# LuMini_3Inch.net
KiCad netlist of a schematic drawn in EAGLE
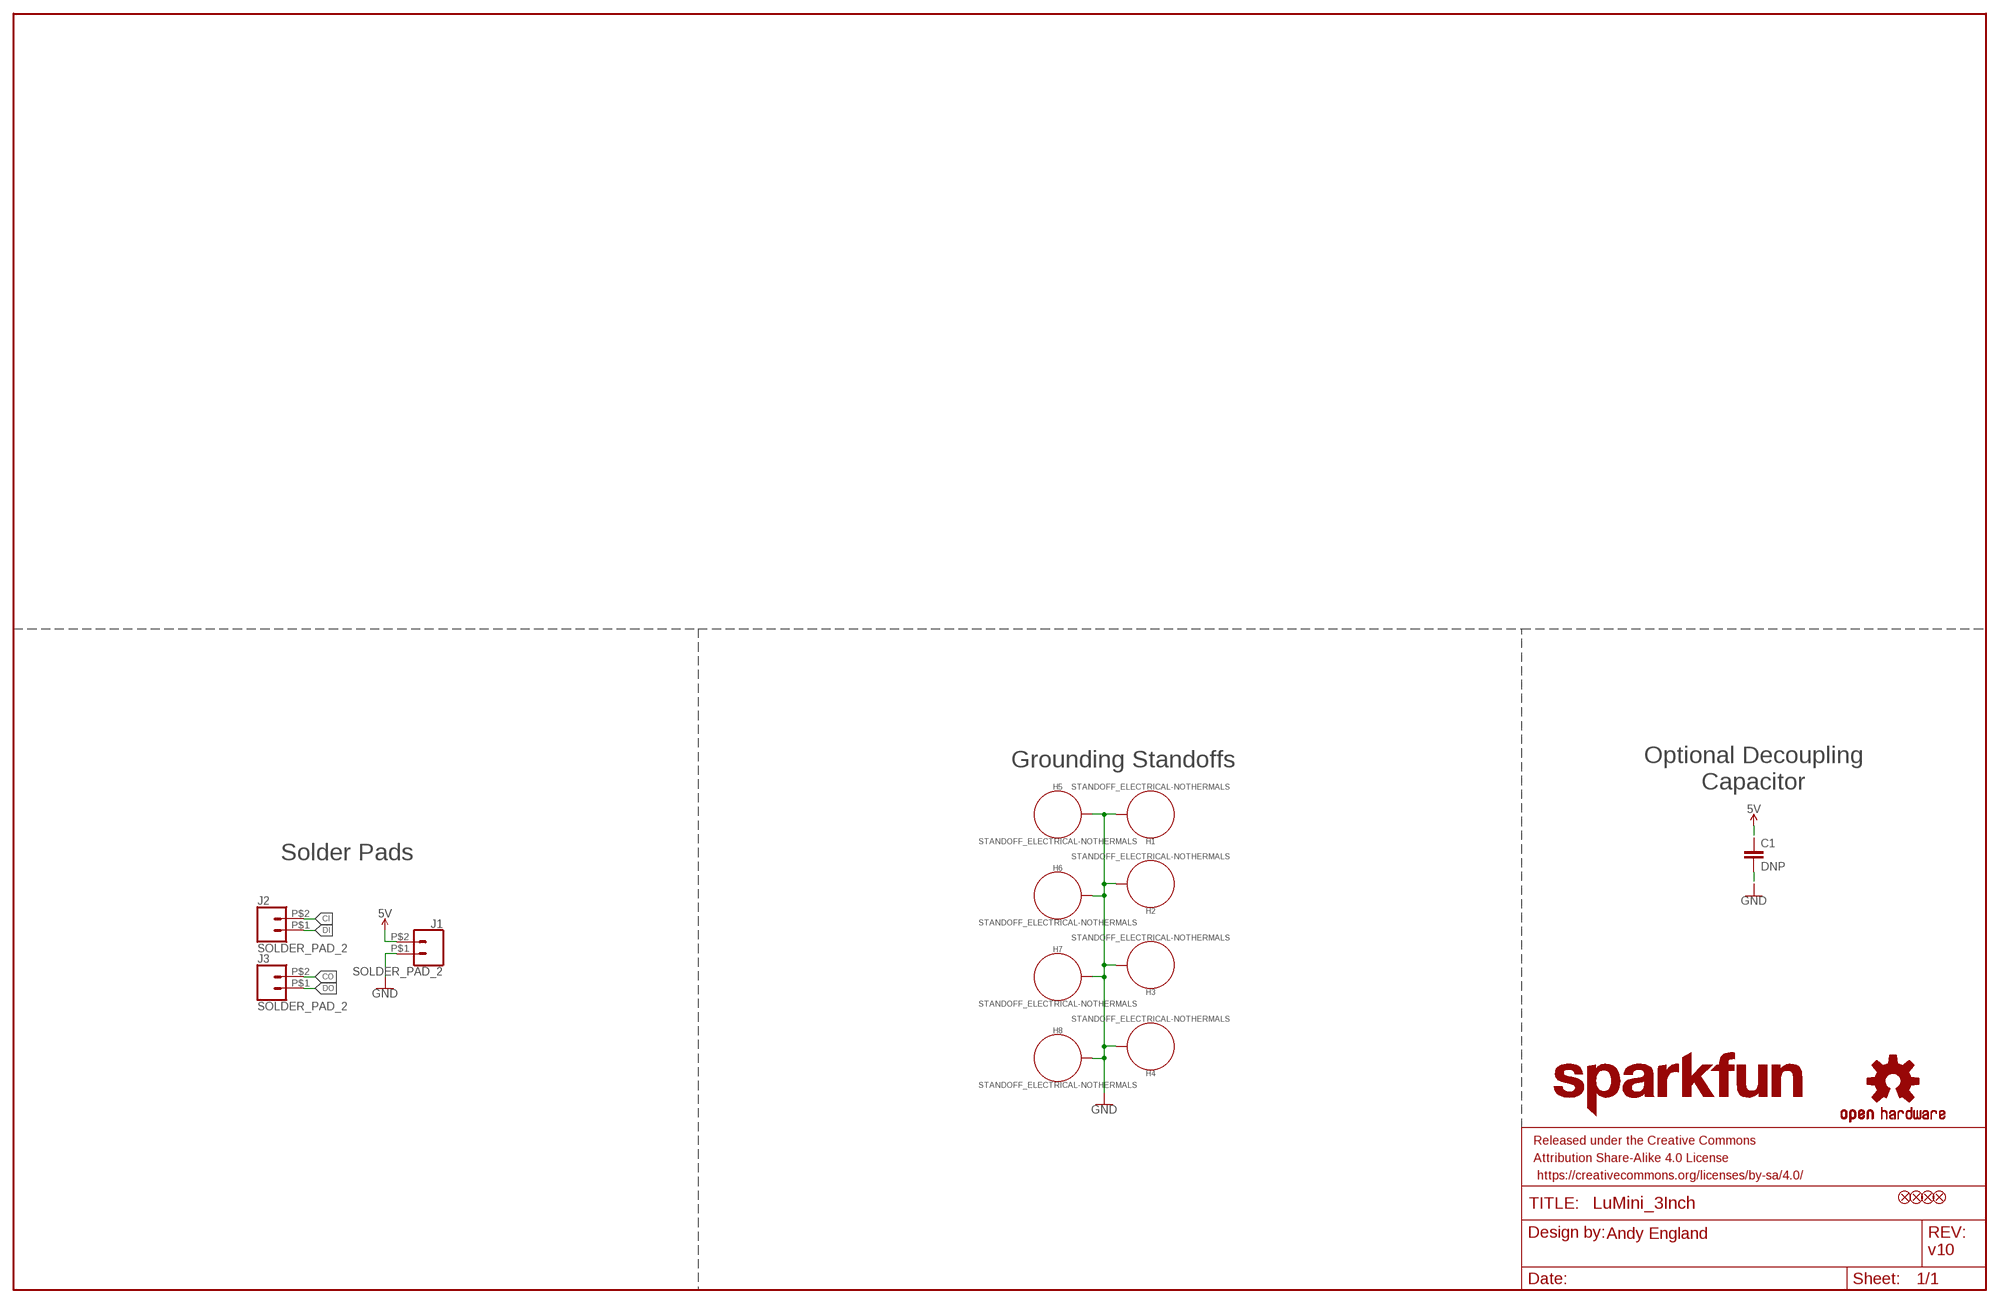
[diagram p0: schematic, sheet 1]

(export (version "E")
  (design (tool "Eeschema 10.0.6"))
  (components
    (comp (ref "C1")
      (value "DNP")
      (footprint "eagle-import:1206")
      (libsource (lib "eagle-import") (part "4.7UF-1206-16V-(+80/-20%)"))
    )
    (comp (ref "FD1")
      (value "FIDUCIALUFIDUCIAL")
      (footprint "eagle-import:FIDUCIAL-MICRO")
      (libsource (lib "eagle-import") (part "FIDUCIALUFIDUCIAL"))
    )
    (comp (ref "FD2")
      (value "FIDUCIALUFIDUCIAL")
      (footprint "eagle-import:FIDUCIAL-MICRO")
      (libsource (lib "eagle-import") (part "FIDUCIALUFIDUCIAL"))
    )
    (comp (ref "FD3")
      (value "FIDUCIALUFIDUCIAL")
      (footprint "eagle-import:FIDUCIAL-MICRO")
      (libsource (lib "eagle-import") (part "FIDUCIALUFIDUCIAL"))
    )
    (comp (ref "FD4")
      (value "FIDUCIALUFIDUCIAL")
      (footprint "eagle-import:FIDUCIAL-MICRO")
      (libsource (lib "eagle-import") (part "FIDUCIALUFIDUCIAL"))
    )
    (comp (ref "FRAME1")
      (value "FRAME-LEDGER")
      (footprint "eagle-import:CREATIVE_COMMONS")
      (libsource (lib "eagle-import") (part "FRAME-LEDGER"))
    )
    (comp (ref "H1")
      (value "STANDOFF_ELECTRICAL-NOTHERMALS")
      (footprint "eagle-import:STANDOFF-ELECTRICAL-NOTHERMALS")
      (libsource (lib "eagle-import") (part "STANDOFF_ELECTRICAL-NOTHERMALS"))
    )
    (comp (ref "H2")
      (value "STANDOFF_ELECTRICAL-NOTHERMALS")
      (footprint "eagle-import:STANDOFF-ELECTRICAL-NOTHERMALS")
      (libsource (lib "eagle-import") (part "STANDOFF_ELECTRICAL-NOTHERMALS"))
    )
    (comp (ref "H3")
      (value "STANDOFF_ELECTRICAL-NOTHERMALS")
      (footprint "eagle-import:STANDOFF-ELECTRICAL-NOTHERMALS")
      (libsource (lib "eagle-import") (part "STANDOFF_ELECTRICAL-NOTHERMALS"))
    )
    (comp (ref "H4")
      (value "STANDOFF_ELECTRICAL-NOTHERMALS")
      (footprint "eagle-import:STANDOFF-ELECTRICAL-NOTHERMALS")
      (libsource (lib "eagle-import") (part "STANDOFF_ELECTRICAL-NOTHERMALS"))
    )
    (comp (ref "H5")
      (value "STANDOFF_ELECTRICAL-NOTHERMALS")
      (footprint "eagle-import:STANDOFF-ELECTRICAL-NOTHERMALS")
      (libsource (lib "eagle-import") (part "STANDOFF_ELECTRICAL-NOTHERMALS"))
    )
    (comp (ref "H6")
      (value "STANDOFF_ELECTRICAL-NOTHERMALS")
      (footprint "eagle-import:STANDOFF-ELECTRICAL-NOTHERMALS")
      (libsource (lib "eagle-import") (part "STANDOFF_ELECTRICAL-NOTHERMALS"))
    )
    (comp (ref "H7")
      (value "STANDOFF_ELECTRICAL-NOTHERMALS")
      (footprint "eagle-import:STANDOFF-ELECTRICAL-NOTHERMALS")
      (libsource (lib "eagle-import") (part "STANDOFF_ELECTRICAL-NOTHERMALS"))
    )
    (comp (ref "H8")
      (value "STANDOFF_ELECTRICAL-NOTHERMALS")
      (footprint "eagle-import:STANDOFF-ELECTRICAL-NOTHERMALS")
      (libsource (lib "eagle-import") (part "STANDOFF_ELECTRICAL-NOTHERMALS"))
    )
    (comp (ref "J1")
      (value "SOLDER_PAD_2")
      (footprint "eagle-import:SOLDER_PAD_2")
      (libsource (lib "eagle-import") (part "SOLDER_PAD_2"))
    )
    (comp (ref "J2")
      (value "SOLDER_PAD_2")
      (footprint "eagle-import:SOLDER_PAD_2")
      (libsource (lib "eagle-import") (part "SOLDER_PAD_2"))
    )
    (comp (ref "J3")
      (value "SOLDER_PAD_2")
      (footprint "eagle-import:SOLDER_PAD_2")
      (libsource (lib "eagle-import") (part "SOLDER_PAD_2"))
    )
    (comp (ref "LOGO1")
      (value "OSHW-LOGOS")
      (footprint "eagle-import:OSHW-LOGO-S")
      (libsource (lib "eagle-import") (part "OSHW-LOGOS"))
    )
    (comp (ref "LOGO2")
      (value "SFE_LOGO_NAME.1_INCH")
      (footprint "eagle-import:SFE_LOGO_NAME_.1")
      (libsource (lib "eagle-import") (part "SFE_LOGO_NAME.1_INCH"))
    )
  )
  (nets
    (net (code "1") (name "5V") (class "Default")
      (node (ref "C1") (pin "1") (pinfunction "1_1") (pintype "passive"))
      (node (ref "J1") (pin "P$2") (pinfunction "2_P$2") (pintype "passive"))
    )
    (net (code "2") (name "CI") (class "Default")
      (node (ref "J2") (pin "P$2") (pinfunction "2_P$2") (pintype "passive"))
    )
    (net (code "3") (name "CO") (class "Default")
      (node (ref "J3") (pin "P$2") (pinfunction "2_P$2") (pintype "passive"))
    )
    (net (code "4") (name "DI") (class "Default")
      (node (ref "J2") (pin "P$1") (pinfunction "1_P$1") (pintype "passive"))
    )
    (net (code "5") (name "DO") (class "Default")
      (node (ref "J3") (pin "P$1") (pinfunction "1_P$1") (pintype "passive"))
    )
    (net (code "6") (name "GND") (class "Default")
      (node (ref "C1") (pin "2") (pinfunction "2_2") (pintype "passive"))
      (node (ref "H1") (pin "P1") (pinfunction "P$1_P1") (pintype "bidirectional"))
      (node (ref "H2") (pin "P1") (pinfunction "P$1_P1") (pintype "bidirectional"))
      (node (ref "H3") (pin "P1") (pinfunction "P$1_P1") (pintype "bidirectional"))
      (node (ref "H4") (pin "P1") (pinfunction "P$1_P1") (pintype "bidirectional"))
      (node (ref "H5") (pin "P1") (pinfunction "P$1_P1") (pintype "bidirectional"))
      (node (ref "H6") (pin "P1") (pinfunction "P$1_P1") (pintype "bidirectional"))
      (node (ref "H7") (pin "P1") (pinfunction "P$1_P1") (pintype "bidirectional"))
      (node (ref "H8") (pin "P1") (pinfunction "P$1_P1") (pintype "bidirectional"))
      (node (ref "J1") (pin "P$1") (pinfunction "1_P$1") (pintype "passive"))
    )
  )
)
